# RelayModule_PWR.net
KiCad netlist of a schematic drawn in Altium Designer
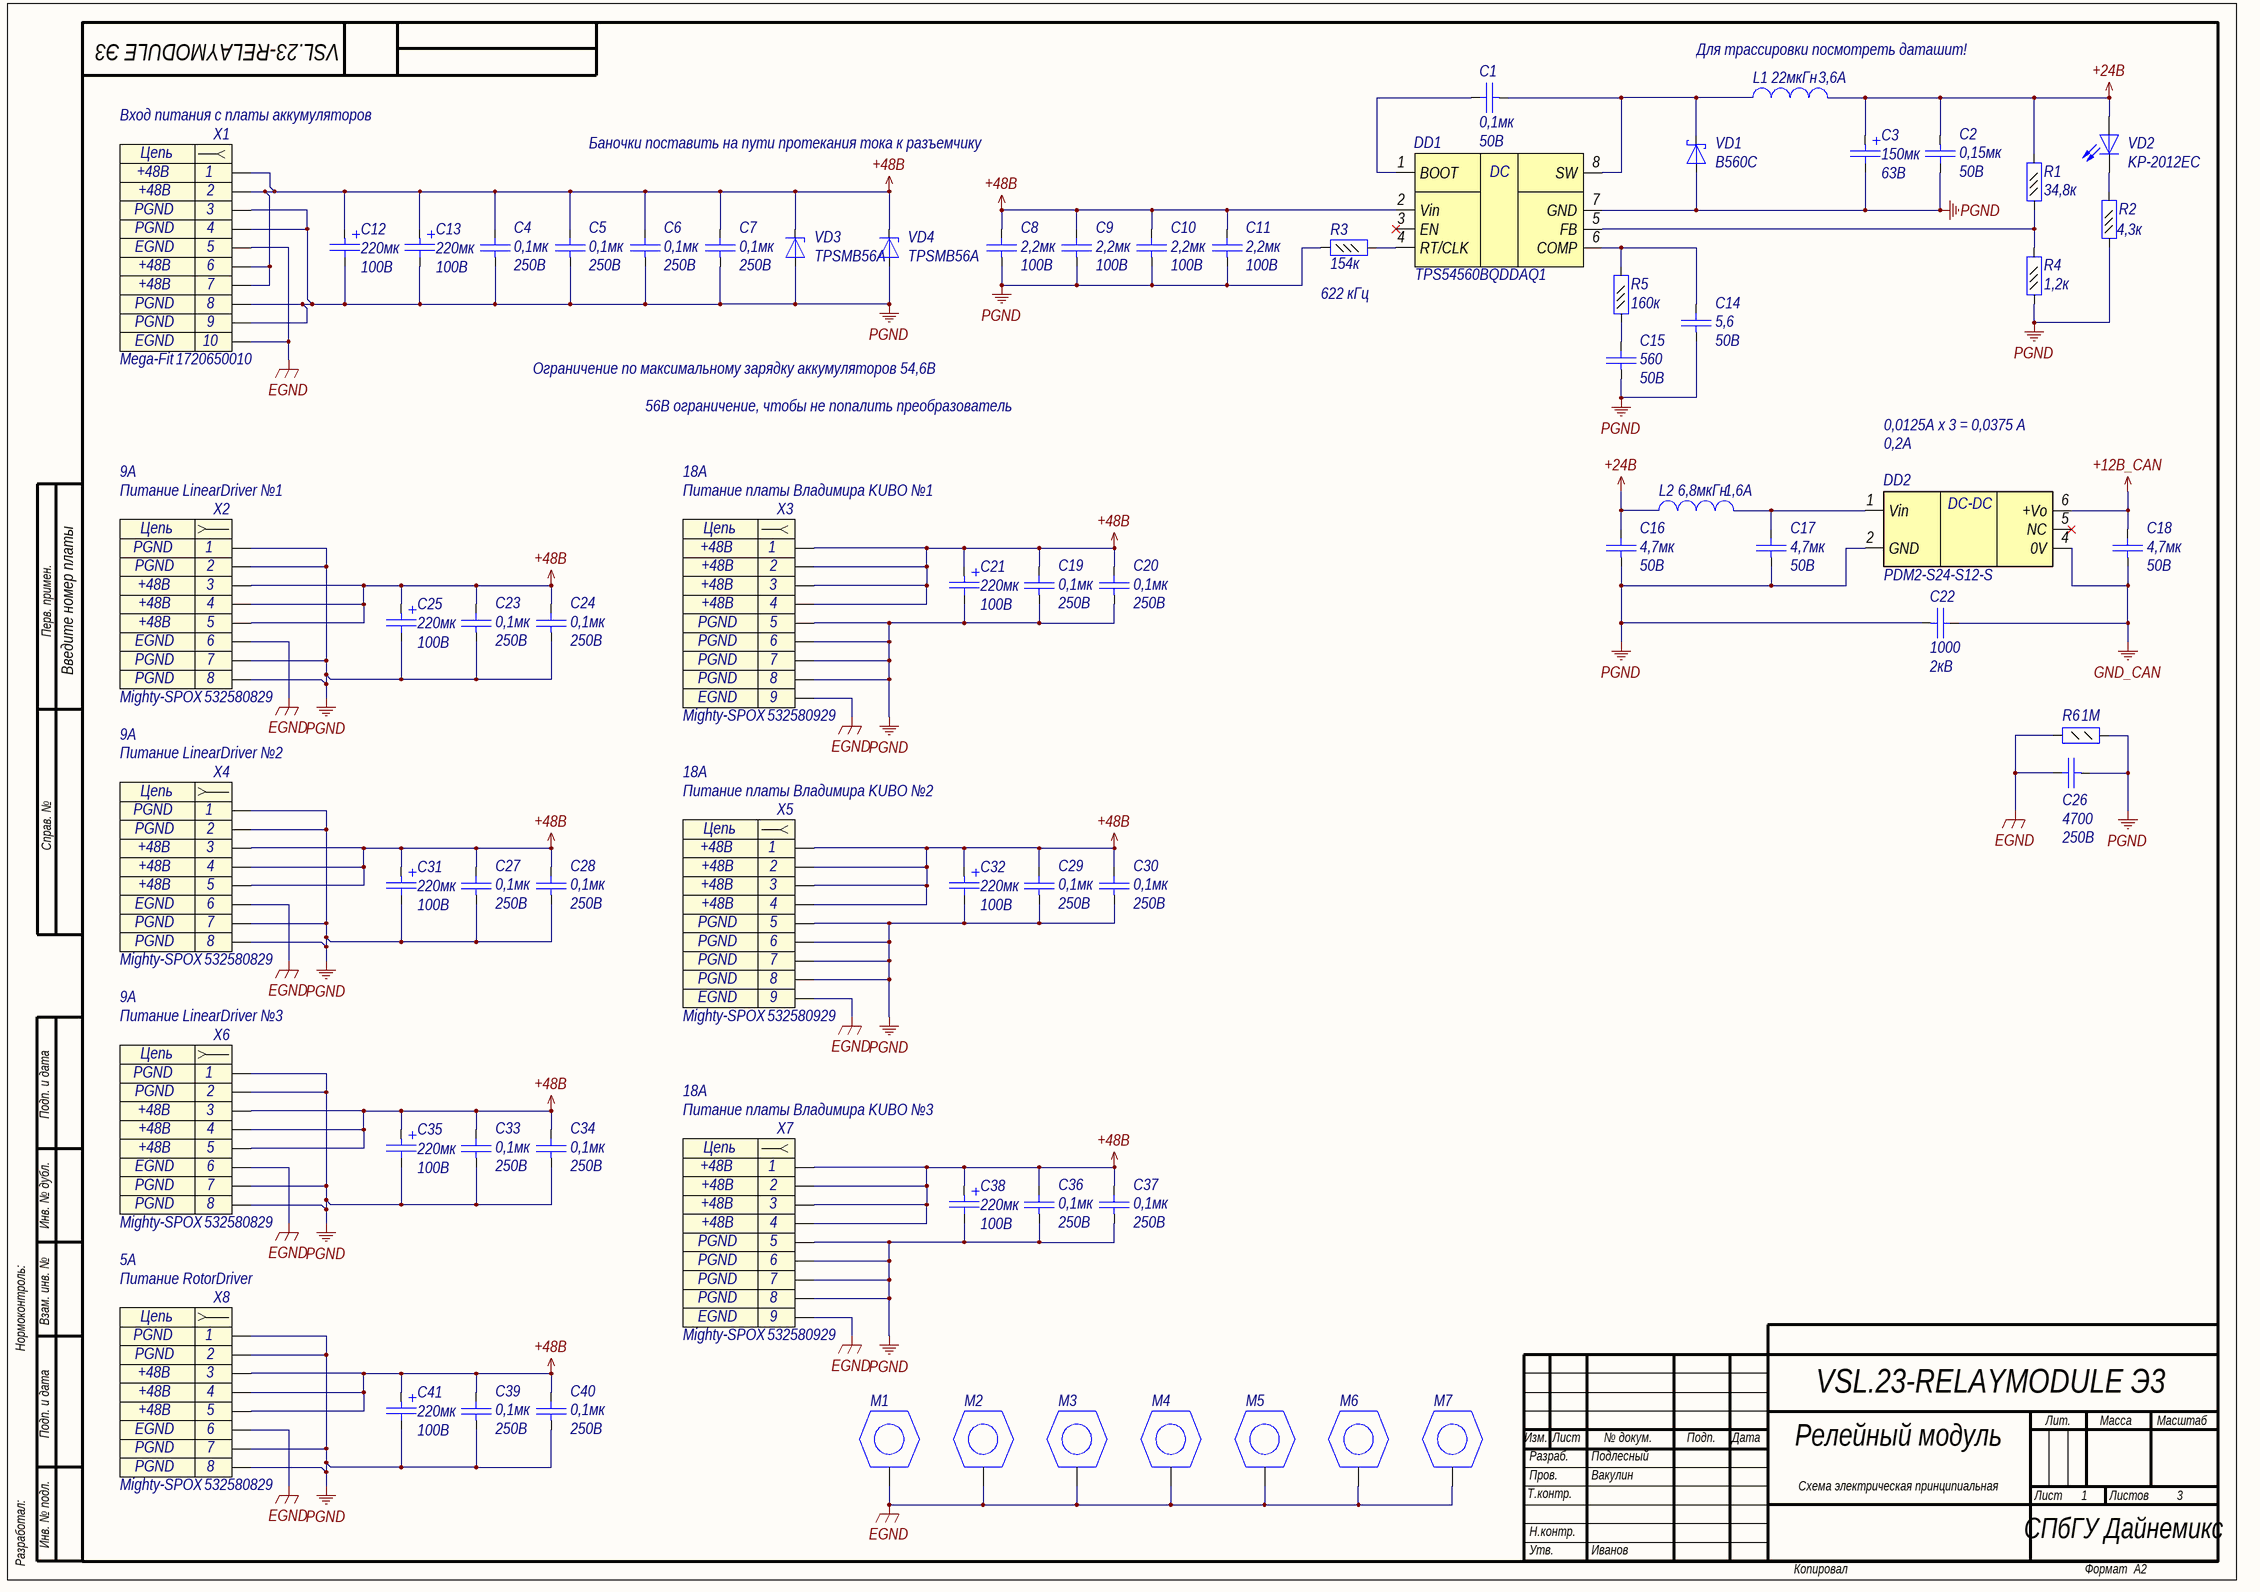
[diagram p0: RelayModule_PWR.SchDoc]

(export (version "E")
  (design (tool "Eeschema 10.0.6"))
  (components
    (comp (ref "C1")
      (value "0,1мк")
      (footprint "C0402")
      (description "Конденсатор")
      (fields (field (name "VOLTAGE") "50В") (field (name "PART NUMBER") "GRM155R71H104KE14D "))
      (libsource (lib "MOP44") (part "Capacitor"))
    )
    (comp (ref "C2")
      (value "0,15мк")
      (footprint "C1812")
      (description "Конденсатор")
      (fields (field (name "VOLTAGE") "50В") (field (name "PART NUMBER") "C4532C0G1H154J250KA "))
      (libsource (lib "MOP44") (part "Capacitor"))
    )
    (comp (ref "C3")
      (value "150мк")
      (footprint "Cap_SMD_radial_polar(10x16.5)")
      (description "Конденсатор полярный")
      (fields
        (field (name "VOLTAGE") "63B")
        (field (name "PART NUMBER") "EEH-ZS1J151P")
        (field (name "Comment") "Capacitor_pol")
      )
      (libsource (lib "MOP44") (part "Capacitor_pol"))
    )
    (comp (ref "C4")
      (value "0,1мк")
      (footprint "C1206")
      (description "Конденсатор")
      (fields
        (field (name "VOLTAGE") "250В")
        (field (name "PART NUMBER") "GRM31CR72E104K")
        (field (name "Comment") "Capacitor")
      )
      (libsource (lib "MOP44") (part "Capacitor"))
    )
    (comp (ref "C5")
      (value "0,1мк")
      (footprint "C1206")
      (description "Конденсатор")
      (fields
        (field (name "VOLTAGE") "250В")
        (field (name "PART NUMBER") "GRM31CR72E104K")
        (field (name "Comment") "Capacitor")
      )
      (libsource (lib "MOP44") (part "Capacitor"))
    )
    (comp (ref "C6")
      (value "0,1мк")
      (footprint "C1206")
      (description "Конденсатор")
      (fields
        (field (name "VOLTAGE") "250В")
        (field (name "PART NUMBER") "GRM31CR72E104K")
        (field (name "Comment") "Capacitor")
      )
      (libsource (lib "MOP44") (part "Capacitor"))
    )
    (comp (ref "C7")
      (value "0,1мк")
      (footprint "C1206")
      (description "Конденсатор")
      (fields
        (field (name "VOLTAGE") "250В")
        (field (name "PART NUMBER") "GRM31CR72E104K")
        (field (name "Comment") "Capacitor")
      )
      (libsource (lib "MOP44") (part "Capacitor"))
    )
    (comp (ref "C8")
      (value "2,2мк")
      (footprint "C1812")
      (description "Конденсатор")
      (fields (field (name "VOLTAGE") "100В") (field (name "PART NUMBER") "C4532X7R2A225M"))
      (libsource (lib "MOP44") (part "Capacitor"))
    )
    (comp (ref "C9")
      (value "2,2мк")
      (footprint "C1812")
      (description "Конденсатор")
      (fields (field (name "VOLTAGE") "100В") (field (name "PART NUMBER") "C4532X7R2A225M"))
      (libsource (lib "MOP44") (part "Capacitor"))
    )
    (comp (ref "C10")
      (value "2,2мк")
      (footprint "C1812")
      (description "Конденсатор")
      (fields (field (name "VOLTAGE") "100В") (field (name "PART NUMBER") "C4532X7R2A225M"))
      (libsource (lib "MOP44") (part "Capacitor"))
    )
    (comp (ref "C11")
      (value "2,2мк")
      (footprint "C1812")
      (description "Конденсатор")
      (fields (field (name "VOLTAGE") "100В") (field (name "PART NUMBER") "C4532X7R2A225M"))
      (libsource (lib "MOP44") (part "Capacitor"))
    )
    (comp (ref "C12")
      (value "220мк")
      (footprint "K50-35(12.5X25)_V")
      (description "Конденсатор полярный")
      (fields
        (field (name "VOLTAGE") "100B")
        (field (name "PART NUMBER") "B41851A9227M000")
        (field (name "Comment") "Capacitor_pol")
      )
      (libsource (lib "MOP44") (part "Capacitor_pol"))
    )
    (comp (ref "C13")
      (value "220мк")
      (footprint "K50-35(12.5X25)_V")
      (description "Конденсатор полярный")
      (fields
        (field (name "VOLTAGE") "100B")
        (field (name "PART NUMBER") "B41851A9227M000")
        (field (name "Comment") "Capacitor_pol")
      )
      (libsource (lib "MOP44") (part "Capacitor_pol"))
    )
    (comp (ref "C14")
      (value "5,6")
      (footprint "C0402")
      (description "Конденсатор")
      (fields (field (name "VOLTAGE") "50B") (field (name "PART NUMBER") "GRM1555C1H5R6C"))
      (libsource (lib "MOP44") (part "Capacitor"))
    )
    (comp (ref "C15")
      (value "560")
      (footprint "C0402")
      (description "Конденсатор")
      (fields (field (name "VOLTAGE") "50B") (field (name "PART NUMBER") "GRM1555C1H561J"))
      (libsource (lib "MOP44") (part "Capacitor"))
    )
    (comp (ref "C16")
      (value "4,7мк")
      (footprint "C1206")
      (description "Конденсатор")
      (fields (field (name "VOLTAGE") "50В") (field (name "PART NUMBER") "GRM31CR71H475KA12L"))
      (libsource (lib "MOP44") (part "Capacitor"))
    )
    (comp (ref "C17")
      (value "4,7мк")
      (footprint "C1206")
      (description "Конденсатор")
      (fields (field (name "VOLTAGE") "50В") (field (name "PART NUMBER") "GRM31CR71H475KA12L"))
      (libsource (lib "MOP44") (part "Capacitor"))
    )
    (comp (ref "C18")
      (value "4,7мк")
      (footprint "C1206")
      (description "Конденсатор")
      (fields (field (name "VOLTAGE") "50В") (field (name "PART NUMBER") "GRM31CR71H475KA12L"))
      (libsource (lib "MOP44") (part "Capacitor"))
    )
    (comp (ref "C19")
      (value "0,1мк")
      (footprint "C1206")
      (description "Конденсатор")
      (fields
        (field (name "VOLTAGE") "250В")
        (field (name "PART NUMBER") "GRM31CR72E104K")
        (field (name "Comment") "Capacitor")
      )
      (libsource (lib "MOP44") (part "Capacitor"))
    )
    (comp (ref "C20")
      (value "0,1мк")
      (footprint "C1206")
      (description "Конденсатор")
      (fields
        (field (name "VOLTAGE") "250В")
        (field (name "PART NUMBER") "GRM31CR72E104K")
        (field (name "Comment") "Capacitor")
      )
      (libsource (lib "MOP44") (part "Capacitor"))
    )
    (comp (ref "C21")
      (value "220мк")
      (footprint "K50-35(12.5X25)_V")
      (description "Конденсатор полярный")
      (fields
        (field (name "VOLTAGE") "100B")
        (field (name "PART NUMBER") "B41851A9227M000")
        (field (name "Comment") "Capacitor_pol")
      )
      (libsource (lib "MOP44") (part "Capacitor_pol"))
    )
    (comp (ref "C22")
      (value "1000")
      (footprint "C1808")
      (description "Конденсатор")
      (fields (field (name "VOLTAGE") "2кB") (field (name "PART NUMBER") "GR442QR73D102KW01L"))
      (libsource (lib "MOP44") (part "Capacitor"))
    )
    (comp (ref "C23")
      (value "0,1мк")
      (footprint "C1206")
      (description "Конденсатор")
      (fields
        (field (name "VOLTAGE") "250В")
        (field (name "PART NUMBER") "GRM31CR72E104K")
        (field (name "Comment") "Capacitor")
      )
      (libsource (lib "MOP44") (part "Capacitor"))
    )
    (comp (ref "C24")
      (value "0,1мк")
      (footprint "C1206")
      (description "Конденсатор")
      (fields
        (field (name "VOLTAGE") "250В")
        (field (name "PART NUMBER") "GRM31CR72E104K")
        (field (name "Comment") "Capacitor")
      )
      (libsource (lib "MOP44") (part "Capacitor"))
    )
    (comp (ref "C25")
      (value "220мк")
      (footprint "K50-35(12.5X25)_V")
      (description "Конденсатор полярный")
      (fields
        (field (name "VOLTAGE") "100B")
        (field (name "PART NUMBER") "B41851A9227M000")
        (field (name "Comment") "Capacitor_pol")
      )
      (libsource (lib "MOP44") (part "Capacitor_pol"))
    )
    (comp (ref "C26")
      (value "4700")
      (footprint "C0805")
      (description "Конденсатор")
      (fields
        (field (name "VOLTAGE") "250В")
        (field (name "PART NUMBER") "GRM21AR72E472KW")
        (field (name "Comment") "Capacitor")
      )
      (libsource (lib "MOP44") (part "Capacitor"))
    )
    (comp (ref "C27")
      (value "0,1мк")
      (footprint "C1206")
      (description "Конденсатор")
      (fields
        (field (name "VOLTAGE") "250В")
        (field (name "PART NUMBER") "GRM31CR72E104K")
        (field (name "Comment") "Capacitor")
      )
      (libsource (lib "MOP44") (part "Capacitor"))
    )
    (comp (ref "C28")
      (value "0,1мк")
      (footprint "C1206")
      (description "Конденсатор")
      (fields
        (field (name "VOLTAGE") "250В")
        (field (name "PART NUMBER") "GRM31CR72E104K")
        (field (name "Comment") "Capacitor")
      )
      (libsource (lib "MOP44") (part "Capacitor"))
    )
    (comp (ref "C29")
      (value "0,1мк")
      (footprint "C1206")
      (description "Конденсатор")
      (fields
        (field (name "VOLTAGE") "250В")
        (field (name "PART NUMBER") "GRM31CR72E104K")
        (field (name "Comment") "Capacitor")
      )
      (libsource (lib "MOP44") (part "Capacitor"))
    )
    (comp (ref "C30")
      (value "0,1мк")
      (footprint "C1206")
      (description "Конденсатор")
      (fields
        (field (name "VOLTAGE") "250В")
        (field (name "PART NUMBER") "GRM31CR72E104K")
        (field (name "Comment") "Capacitor")
      )
      (libsource (lib "MOP44") (part "Capacitor"))
    )
    (comp (ref "C31")
      (value "220мк")
      (footprint "K50-35(12.5X25)_V")
      (description "Конденсатор полярный")
      (fields
        (field (name "VOLTAGE") "100B")
        (field (name "PART NUMBER") "B41851A9227M000")
        (field (name "Comment") "Capacitor_pol")
      )
      (libsource (lib "MOP44") (part "Capacitor_pol"))
    )
    (comp (ref "C32")
      (value "220мк")
      (footprint "K50-35(12.5X25)_V")
      (description "Конденсатор полярный")
      (fields
        (field (name "VOLTAGE") "100B")
        (field (name "PART NUMBER") "B41851A9227M000")
        (field (name "Comment") "Capacitor_pol")
      )
      (libsource (lib "MOP44") (part "Capacitor_pol"))
    )
    (comp (ref "C33")
      (value "0,1мк")
      (footprint "C1206")
      (description "Конденсатор")
      (fields
        (field (name "VOLTAGE") "250В")
        (field (name "PART NUMBER") "GRM31CR72E104K")
        (field (name "Comment") "Capacitor")
      )
      (libsource (lib "MOP44") (part "Capacitor"))
    )
    (comp (ref "C34")
      (value "0,1мк")
      (footprint "C1206")
      (description "Конденсатор")
      (fields
        (field (name "VOLTAGE") "250В")
        (field (name "PART NUMBER") "GRM31CR72E104K")
        (field (name "Comment") "Capacitor")
      )
      (libsource (lib "MOP44") (part "Capacitor"))
    )
    (comp (ref "C35")
      (value "220мк")
      (footprint "K50-35(12.5X25)_V")
      (description "Конденсатор полярный")
      (fields
        (field (name "VOLTAGE") "100B")
        (field (name "PART NUMBER") "B41851A9227M000")
        (field (name "Comment") "Capacitor_pol")
      )
      (libsource (lib "MOP44") (part "Capacitor_pol"))
    )
    (comp (ref "C36")
      (value "0,1мк")
      (footprint "C1206")
      (description "Конденсатор")
      (fields
        (field (name "VOLTAGE") "250В")
        (field (name "PART NUMBER") "GRM31CR72E104K")
        (field (name "Comment") "Capacitor")
      )
      (libsource (lib "MOP44") (part "Capacitor"))
    )
    (comp (ref "C37")
      (value "0,1мк")
      (footprint "C1206")
      (description "Конденсатор")
      (fields
        (field (name "VOLTAGE") "250В")
        (field (name "PART NUMBER") "GRM31CR72E104K")
        (field (name "Comment") "Capacitor")
      )
      (libsource (lib "MOP44") (part "Capacitor"))
    )
    (comp (ref "C38")
      (value "220мк")
      (footprint "K50-35(12.5X25)_V")
      (description "Конденсатор полярный")
      (fields
        (field (name "VOLTAGE") "100B")
        (field (name "PART NUMBER") "B41851A9227M000")
        (field (name "Comment") "Capacitor_pol")
      )
      (libsource (lib "MOP44") (part "Capacitor_pol"))
    )
    (comp (ref "C39")
      (value "0,1мк")
      (footprint "C1206")
      (description "Конденсатор")
      (fields
        (field (name "VOLTAGE") "250В")
        (field (name "PART NUMBER") "GRM31CR72E104K")
        (field (name "Comment") "Capacitor")
      )
      (libsource (lib "MOP44") (part "Capacitor"))
    )
    (comp (ref "C40")
      (value "0,1мк")
      (footprint "C1206")
      (description "Конденсатор")
      (fields
        (field (name "VOLTAGE") "250В")
        (field (name "PART NUMBER") "GRM31CR72E104K")
        (field (name "Comment") "Capacitor")
      )
      (libsource (lib "MOP44") (part "Capacitor"))
    )
    (comp (ref "C41")
      (value "220мк")
      (footprint "K50-35(12.5X25)_V")
      (description "Конденсатор полярный")
      (fields
        (field (name "VOLTAGE") "100B")
        (field (name "PART NUMBER") "B41851A9227M000")
        (field (name "Comment") "Capacitor_pol")
      )
      (libsource (lib "MOP44") (part "Capacitor_pol"))
    )
    (comp (ref "DD1")
      (value "TPS54560")
      (footprint "SO Powerpad8")
      (description "5-A, Wide Input Range, Step-Down Converter")
      (fields
        (field (name "PART NUMBER") "TPS54560BQDDAQ1")
        (field (name "MANUFACTURER") "Texas Instruments")
      )
      (libsource (lib "MOP44") (part "TPS54560"))
    )
    (comp (ref "DD2")
      (value "PDM2-Sxx-Sxx-S")
      (footprint "SIP6")
      (description "DC/DC преобразователь изолированный")
      (fields (field (name "PART NUMBER") "PDM2-S24-S12-S") (field (name "MANUFACTURER") "CUI INC"))
      (libsource (lib "MOP44") (part "PDM2-Sxx-Sxx-S"))
    )
    (comp (ref "L1")
      (value "22мкГн")
      (footprint "IND_12.5x12.5")
      (description "EMI Suppression Filter")
      (fields
        (field (name "RATED CURRENT") "3,6A")
        (field (name "PART NUMBER") "B82477G4223M000")
        (field (name "Comment") "Inductor")
      )
      (libsource (lib "MOP44") (part "Inductor"))
    )
    (comp (ref "L2")
      (value "6,8мкГн")
      (footprint "SDR0604")
      (description "EMI Suppression Filter")
      (fields
        (field (name "RATED CURRENT") "1,6A")
        (field (name "PART NUMBER") "SDR0604-6R8ML")
        (field (name "Comment") "Inductor")
      )
      (libsource (lib "MOP44") (part "Inductor"))
    )
    (comp (ref "M1") (value "SCREW") (footprint "SCREW3") (libsource (lib "MOP44") (part "SCREW")))
    (comp (ref "M2") (value "SCREW") (footprint "SCREW3") (libsource (lib "MOP44") (part "SCREW")))
    (comp (ref "M3") (value "SCREW") (footprint "SCREW3") (libsource (lib "MOP44") (part "SCREW")))
    (comp (ref "M4") (value "SCREW") (footprint "SCREW3") (libsource (lib "MOP44") (part "SCREW")))
    (comp (ref "M5") (value "SCREW") (footprint "SCREW3") (libsource (lib "MOP44") (part "SCREW")))
    (comp (ref "M6") (value "SCREW") (footprint "SCREW3") (libsource (lib "MOP44") (part "SCREW")))
    (comp (ref "M7") (value "SCREW") (footprint "SCREW3") (libsource (lib "MOP44") (part "SCREW")))
    (comp (ref "R1")
      (value "34,8к")
      (footprint "R0402")
      (description "Резистор")
      (fields (field (name "PART NUMBER") "RC0402FR-0734K8L") (field (name "POWER") "0,062Вт"))
      (libsource (lib "MOP44") (part "Resistor_0,062Вт"))
    )
    (comp (ref "R2")
      (value "4,3к")
      (footprint "R0402")
      (description "Резистор")
      (fields (field (name "PART NUMBER") "RC0402FR-074K3") (field (name "POWER") "0,062Вт"))
      (libsource (lib "MOP44") (part "Resistor_0,062Вт"))
    )
    (comp (ref "R3")
      (value "154к")
      (footprint "R0402")
      (description "Резистор")
      (fields (field (name "PART NUMBER") "RC0402FR-07154KL") (field (name "POWER") "0,062Вт"))
      (libsource (lib "") (part "Resistor_0,062Вт_1"))
    )
    (comp (ref "R4")
      (value "1,2к")
      (footprint "R0402")
      (description "Резистор")
      (fields (field (name "PART NUMBER") "RC0402FR-071K2") (field (name "POWER") "0,062Вт"))
      (libsource (lib "MOP44") (part "Resistor_0,062Вт"))
    )
    (comp (ref "R5")
      (value "160к")
      (footprint "R0402")
      (description "Резистор")
      (fields (field (name "PART NUMBER") "RC0402FR-07160KL") (field (name "POWER") "0,062Вт"))
      (libsource (lib "MOP44") (part "Resistor_0,062Вт"))
    )
    (comp (ref "R6")
      (value "1М")
      (footprint "R0805")
      (description "Резистор")
      (fields (field (name "PART NUMBER") "RC0805FR-071ML") (field (name "POWER") "0,125Вт"))
      (libsource (lib "MOP44") (part "Resistor_0,125Вт"))
    )
    (comp (ref "VD1")
      (value "DiodeSchottky")
      (footprint "SMC")
      (description "Диод Шоттки")
      (fields (field (name "PART NUMBER") "B560C"))
      (libsource (lib "MOP44") (part "DiodeSchottky"))
    )
    (comp (ref "VD2")
      (value "LED")
      (footprint "L_0805")
      (description "Светодиод")
      (fields (field (name "PART NUMBER") "KP-2012EC"))
      (libsource (lib "MOP44") (part "LED"))
    )
    (comp (ref "VD3")
      (value "DiodeZener")
      (footprint "SMB")
      (description "Cтабилитрон (лавинный выпрямительный диод) односторонний")
      (fields (field (name "PART NUMBER") "TPSMB56A"))
      (libsource (lib "MOP44") (part "DiodeZener"))
    )
    (comp (ref "VD4")
      (value "DiodeZener")
      (footprint "SMB")
      (description "Cтабилитрон (лавинный выпрямительный диод) односторонний")
      (fields (field (name "PART NUMBER") "TPSMB56A"))
      (libsource (lib "MOP44") (part "DiodeZener"))
    )
    (comp (ref "X1")
      (value "Вход питания с платы аккумуляторов")
      (footprint "MOLEX_1720650010")
      (description "Разъем - 10 конт. розетка")
      (fields (field (name "PART NAME") "Mega-Fit") (field (name "PART NUMBER") "1720650010"))
      (libsource (lib "MOP44") (part "Header_10_sct"))
    )
    (comp (ref "X2")
      (value "Питание LinearDriver №1")
      (footprint "MOLEX_532580829")
      (description "Разъем - 8 конт. розетка")
      (fields (field (name "PART NAME") "Mighty-SPOX") (field (name "PART NUMBER") "532580829"))
      (libsource (lib "MOP44") (part "Header_8_sct"))
    )
    (comp (ref "X3")
      (value "Питание платы Владимира KUBO №1")
      (footprint "MOLEX_532580929")
      (description "Разъем - 9 конт. розетка")
      (fields (field (name "PART NAME") "Mighty-SPOX") (field (name "PART NUMBER") "532580929"))
      (libsource (lib "MOP44") (part "Header_9_sct"))
    )
    (comp (ref "X4")
      (value "Питание LinearDriver №2")
      (footprint "MOLEX_532580829")
      (description "Разъем - 8 конт. розетка")
      (fields (field (name "PART NAME") "Mighty-SPOX") (field (name "PART NUMBER") "532580829"))
      (libsource (lib "MOP44") (part "Header_8_sct"))
    )
    (comp (ref "X5")
      (value "Питание платы Владимира KUBO №2")
      (footprint "MOLEX_532580929")
      (description "Разъем - 9 конт. розетка")
      (fields (field (name "PART NAME") "Mighty-SPOX") (field (name "PART NUMBER") "532580929"))
      (libsource (lib "MOP44") (part "Header_9_sct"))
    )
    (comp (ref "X6")
      (value "Питание LinearDriver №3")
      (footprint "MOLEX_532580829")
      (description "Разъем - 8 конт. розетка")
      (fields (field (name "PART NAME") "Mighty-SPOX") (field (name "PART NUMBER") "532580829"))
      (libsource (lib "MOP44") (part "Header_8_sct"))
    )
    (comp (ref "X7")
      (value "Питание платы Владимира KUBO №3")
      (footprint "MOLEX_532580929")
      (description "Разъем - 9 конт. розетка")
      (fields (field (name "PART NAME") "Mighty-SPOX") (field (name "PART NUMBER") "532580929"))
      (libsource (lib "MOP44") (part "Header_9_sct"))
    )
    (comp (ref "X8")
      (value "Питание RotorDriver")
      (footprint "MOLEX_532580829")
      (description "Разъем - 8 конт. розетка")
      (fields (field (name "PART NAME") "Mighty-SPOX") (field (name "PART NUMBER") "532580829"))
      (libsource (lib "MOP44") (part "Header_8_sct"))
    )
  )
  (nets
    (net (code "1") (name "+12B_CAN") (class "Default")
      (node (ref "C18") (pin "2") (pinfunction "2_2") (pintype "passive"))
      (node (ref "DD2") (pin "6") (pinfunction "+Vo_6") (pintype "passive"))
    )
    (net (code "2") (name "+24B") (class "Default")
      (node (ref "C16") (pin "2") (pinfunction "2_2") (pintype "passive"))
      (node (ref "C2") (pin "1") (pinfunction "1_1") (pintype "passive"))
      (node (ref "C3") (pin "1") (pinfunction "1_1") (pintype "passive"))
      (node (ref "L1") (pin "2") (pinfunction "2_2") (pintype "passive"))
      (node (ref "L2") (pin "1") (pinfunction "1_1") (pintype "passive"))
      (node (ref "R1") (pin "2") (pinfunction "2_2") (pintype "passive"))
      (node (ref "VD2") (pin "2") (pinfunction "A_2") (pintype "passive"))
    )
    (net (code "3") (name "+48B") (class "Default")
      (node (ref "C10") (pin "2") (pinfunction "2_2") (pintype "passive"))
      (node (ref "C11") (pin "2") (pinfunction "2_2") (pintype "passive"))
      (node (ref "C12") (pin "1") (pinfunction "1_1") (pintype "passive"))
      (node (ref "C13") (pin "1") (pinfunction "1_1") (pintype "passive"))
      (node (ref "C19") (pin "2") (pinfunction "2_2") (pintype "passive"))
      (node (ref "C20") (pin "2") (pinfunction "2_2") (pintype "passive"))
      (node (ref "C21") (pin "1") (pinfunction "1_1") (pintype "passive"))
      (node (ref "C23") (pin "2") (pinfunction "2_2") (pintype "passive"))
      (node (ref "C24") (pin "2") (pinfunction "2_2") (pintype "passive"))
      (node (ref "C25") (pin "1") (pinfunction "1_1") (pintype "passive"))
      (node (ref "C27") (pin "2") (pinfunction "2_2") (pintype "passive"))
      (node (ref "C28") (pin "2") (pinfunction "2_2") (pintype "passive"))
      (node (ref "C29") (pin "2") (pinfunction "2_2") (pintype "passive"))
      (node (ref "C30") (pin "2") (pinfunction "2_2") (pintype "passive"))
      (node (ref "C31") (pin "1") (pinfunction "1_1") (pintype "passive"))
      (node (ref "C32") (pin "1") (pinfunction "1_1") (pintype "passive"))
      (node (ref "C33") (pin "2") (pinfunction "2_2") (pintype "passive"))
      (node (ref "C34") (pin "2") (pinfunction "2_2") (pintype "passive"))
      (node (ref "C35") (pin "1") (pinfunction "1_1") (pintype "passive"))
      (node (ref "C36") (pin "2") (pinfunction "2_2") (pintype "passive"))
      (node (ref "C37") (pin "2") (pinfunction "2_2") (pintype "passive"))
      (node (ref "C38") (pin "1") (pinfunction "1_1") (pintype "passive"))
      (node (ref "C39") (pin "2") (pinfunction "2_2") (pintype "passive"))
      (node (ref "C4") (pin "2") (pinfunction "2_2") (pintype "passive"))
      (node (ref "C40") (pin "2") (pinfunction "2_2") (pintype "passive"))
      (node (ref "C41") (pin "1") (pinfunction "1_1") (pintype "passive"))
      (node (ref "C5") (pin "2") (pinfunction "2_2") (pintype "passive"))
      (node (ref "C6") (pin "2") (pinfunction "2_2") (pintype "passive"))
      (node (ref "C7") (pin "2") (pinfunction "2_2") (pintype "passive"))
      (node (ref "C8") (pin "2") (pinfunction "2_2") (pintype "passive"))
      (node (ref "C9") (pin "2") (pinfunction "2_2") (pintype "passive"))
      (node (ref "DD1") (pin "2") (pinfunction "Vin_2") (pintype "passive"))
      (node (ref "VD3") (pin "1") (pinfunction "K_1") (pintype "passive"))
      (node (ref "VD4") (pin "1") (pinfunction "K_1") (pintype "passive"))
      (node (ref "X1") (pin "1") (pinfunction "1_1") (pintype "passive"))
      (node (ref "X1") (pin "2") (pinfunction "2_2") (pintype "passive"))
      (node (ref "X1") (pin "6") (pinfunction "6_6") (pintype "passive"))
      (node (ref "X1") (pin "7") (pinfunction "7_7") (pintype "passive"))
      (node (ref "X2") (pin "3") (pinfunction "3_3") (pintype "passive"))
      (node (ref "X2") (pin "4") (pinfunction "4_4") (pintype "passive"))
      (node (ref "X2") (pin "5") (pinfunction "5_5") (pintype "passive"))
      (node (ref "X3") (pin "1") (pinfunction "1_1") (pintype "passive"))
      (node (ref "X3") (pin "2") (pinfunction "2_2") (pintype "passive"))
      (node (ref "X3") (pin "3") (pinfunction "3_3") (pintype "passive"))
      (node (ref "X3") (pin "4") (pinfunction "4_4") (pintype "passive"))
      (node (ref "X4") (pin "3") (pinfunction "3_3") (pintype "passive"))
      (node (ref "X4") (pin "4") (pinfunction "4_4") (pintype "passive"))
      (node (ref "X4") (pin "5") (pinfunction "5_5") (pintype "passive"))
      (node (ref "X5") (pin "1") (pinfunction "1_1") (pintype "passive"))
      (node (ref "X5") (pin "2") (pinfunction "2_2") (pintype "passive"))
      (node (ref "X5") (pin "3") (pinfunction "3_3") (pintype "passive"))
      (node (ref "X5") (pin "4") (pinfunction "4_4") (pintype "passive"))
      (node (ref "X6") (pin "3") (pinfunction "3_3") (pintype "passive"))
      (node (ref "X6") (pin "4") (pinfunction "4_4") (pintype "passive"))
      (node (ref "X6") (pin "5") (pinfunction "5_5") (pintype "passive"))
      (node (ref "X7") (pin "1") (pinfunction "1_1") (pintype "passive"))
      (node (ref "X7") (pin "2") (pinfunction "2_2") (pintype "passive"))
      (node (ref "X7") (pin "3") (pinfunction "3_3") (pintype "passive"))
      (node (ref "X7") (pin "4") (pinfunction "4_4") (pintype "passive"))
      (node (ref "X8") (pin "3") (pinfunction "3_3") (pintype "passive"))
      (node (ref "X8") (pin "4") (pinfunction "4_4") (pintype "passive"))
      (node (ref "X8") (pin "5") (pinfunction "5_5") (pintype "passive"))
    )
    (net (code "4") (name "EGND") (class "Default")
      (node (ref "C26") (pin "2") (pinfunction "2_2") (pintype "passive"))
      (node (ref "M1") (pin "1") (pinfunction "1_1") (pintype "passive"))
      (node (ref "M2") (pin "1") (pinfunction "1_1") (pintype "passive"))
      (node (ref "M3") (pin "1") (pinfunction "1_1") (pintype "passive"))
      (node (ref "M4") (pin "1") (pinfunction "1_1") (pintype "passive"))
      (node (ref "M5") (pin "1") (pinfunction "1_1") (pintype "passive"))
      (node (ref "M6") (pin "1") (pinfunction "1_1") (pintype "passive"))
      (node (ref "M7") (pin "1") (pinfunction "1_1") (pintype "passive"))
      (node (ref "R6") (pin "2") (pinfunction "2_2") (pintype "passive"))
      (node (ref "X1") (pin "10") (pinfunction "10_10") (pintype "passive"))
      (node (ref "X1") (pin "5") (pinfunction "5_5") (pintype "passive"))
      (node (ref "X2") (pin "6") (pinfunction "6_6") (pintype "passive"))
      (node (ref "X3") (pin "9") (pinfunction "9_9") (pintype "passive"))
      (node (ref "X4") (pin "6") (pinfunction "6_6") (pintype "passive"))
      (node (ref "X5") (pin "9") (pinfunction "9_9") (pintype "passive"))
      (node (ref "X6") (pin "6") (pinfunction "6_6") (pintype "passive"))
      (node (ref "X7") (pin "9") (pinfunction "9_9") (pintype "passive"))
      (node (ref "X8") (pin "6") (pinfunction "6_6") (pintype "passive"))
    )
    (net (code "5") (name "GND_CAN") (class "Default")
      (node (ref "C18") (pin "1") (pinfunction "1_1") (pintype "passive"))
      (node (ref "C22") (pin "2") (pinfunction "2_2") (pintype "passive"))
      (node (ref "DD2") (pin "4") (pinfunction "0V_4") (pintype "passive"))
    )
    (net (code "6") (name "Net-(C15-Pad2)") (class "Default")
      (node (ref "C15") (pin "2") (pinfunction "2_2") (pintype "passive"))
      (node (ref "R5") (pin "1") (pinfunction "1_1") (pintype "passive"))
    )
    (net (code "7") (name "Net-(DD1-BOOT)") (class "Default")
      (node (ref "C1") (pin "2") (pinfunction "2_2") (pintype "passive"))
      (node (ref "DD1") (pin "1") (pinfunction "BOOT_1") (pintype "passive"))
    )
    (net (code "8") (name "Net-(DD1-COMP)") (class "Default")
      (node (ref "C14") (pin "2") (pinfunction "2_2") (pintype "passive"))
      (node (ref "DD1") (pin "6") (pinfunction "COMP_6") (pintype "passive"))
      (node (ref "R5") (pin "2") (pinfunction "2_2") (pintype "passive"))
    )
    (net (code "9") (name "Net-(DD1-FB)") (class "Default")
      (node (ref "DD1") (pin "5") (pinfunction "FB_5") (pintype "passive"))
      (node (ref "R1") (pin "1") (pinfunction "1_1") (pintype "passive"))
      (node (ref "R4") (pin "2") (pinfunction "2_2") (pintype "passive"))
    )
    (net (code "10") (name "Net-(DD1-RT{slash}CLK)") (class "Default")
      (node (ref "DD1") (pin "4") (pinfunction "RT/CLK_4") (pintype "passive"))
      (node (ref "R3") (pin "2") (pinfunction "2_2") (pintype "passive"))
    )
    (net (code "11") (name "Net-(DD1-SW)") (class "Default")
      (node (ref "C1") (pin "1") (pinfunction "1_1") (pintype "passive"))
      (node (ref "DD1") (pin "8") (pinfunction "SW_8") (pintype "passive"))
      (node (ref "L1") (pin "1") (pinfunction "1_1") (pintype "passive"))
      (node (ref "VD1") (pin "1") (pinfunction "K_1") (pintype "passive"))
    )
    (net (code "12") (name "Net-(DD2-Vin)") (class "Default")
      (node (ref "C17") (pin "2") (pinfunction "2_2") (pintype "passive"))
      (node (ref "DD2") (pin "1") (pinfunction "Vin_1") (pintype "passive"))
      (node (ref "L2") (pin "2") (pinfunction "2_2") (pintype "passive"))
    )
    (net (code "13") (name "Net-(VD2-K)") (class "Default")
      (node (ref "R2") (pin "2") (pinfunction "2_2") (pintype "passive"))
      (node (ref "VD2") (pin "1") (pinfunction "K_1") (pintype "passive"))
    )
    (net (code "14") (name "PGND") (class "Default")
      (node (ref "C10") (pin "1") (pinfunction "1_1") (pintype "passive"))
      (node (ref "C11") (pin "1") (pinfunction "1_1") (pintype "passive"))
      (node (ref "C12") (pin "2") (pinfunction "2_2") (pintype "passive"))
      (node (ref "C13") (pin "2") (pinfunction "2_2") (pintype "passive"))
      (node (ref "C14") (pin "1") (pinfunction "1_1") (pintype "passive"))
      (node (ref "C15") (pin "1") (pinfunction "1_1") (pintype "passive"))
      (node (ref "C16") (pin "1") (pinfunction "1_1") (pintype "passive"))
      (node (ref "C17") (pin "1") (pinfunction "1_1") (pintype "passive"))
      (node (ref "C19") (pin "1") (pinfunction "1_1") (pintype "passive"))
      (node (ref "C2") (pin "2") (pinfunction "2_2") (pintype "passive"))
      (node (ref "C20") (pin "1") (pinfunction "1_1") (pintype "passive"))
      (node (ref "C21") (pin "2") (pinfunction "2_2") (pintype "passive"))
      (node (ref "C22") (pin "1") (pinfunction "1_1") (pintype "passive"))
      (node (ref "C23") (pin "1") (pinfunction "1_1") (pintype "passive"))
      (node (ref "C24") (pin "1") (pinfunction "1_1") (pintype "passive"))
      (node (ref "C25") (pin "2") (pinfunction "2_2") (pintype "passive"))
      (node (ref "C26") (pin "1") (pinfunction "1_1") (pintype "passive"))
      (node (ref "C27") (pin "1") (pinfunction "1_1") (pintype "passive"))
      (node (ref "C28") (pin "1") (pinfunction "1_1") (pintype "passive"))
      (node (ref "C29") (pin "1") (pinfunction "1_1") (pintype "passive"))
      (node (ref "C3") (pin "2") (pinfunction "2_2") (pintype "passive"))
      (node (ref "C30") (pin "1") (pinfunction "1_1") (pintype "passive"))
      (node (ref "C31") (pin "2") (pinfunction "2_2") (pintype "passive"))
      (node (ref "C32") (pin "2") (pinfunction "2_2") (pintype "passive"))
      (node (ref "C33") (pin "1") (pinfunction "1_1") (pintype "passive"))
      (node (ref "C34") (pin "1") (pinfunction "1_1") (pintype "passive"))
      (node (ref "C35") (pin "2") (pinfunction "2_2") (pintype "passive"))
      (node (ref "C36") (pin "1") (pinfunction "1_1") (pintype "passive"))
      (node (ref "C37") (pin "1") (pinfunction "1_1") (pintype "passive"))
      (node (ref "C38") (pin "2") (pinfunction "2_2") (pintype "passive"))
      (node (ref "C39") (pin "1") (pinfunction "1_1") (pintype "passive"))
      (node (ref "C4") (pin "1") (pinfunction "1_1") (pintype "passive"))
      (node (ref "C40") (pin "1") (pinfunction "1_1") (pintype "passive"))
      (node (ref "C41") (pin "2") (pinfunction "2_2") (pintype "passive"))
      (node (ref "C5") (pin "1") (pinfunction "1_1") (pintype "passive"))
      (node (ref "C6") (pin "1") (pinfunction "1_1") (pintype "passive"))
      (node (ref "C7") (pin "1") (pinfunction "1_1") (pintype "passive"))
      (node (ref "C8") (pin "1") (pinfunction "1_1") (pintype "passive"))
      (node (ref "C9") (pin "1") (pinfunction "1_1") (pintype "passive"))
      (node (ref "DD1") (pin "7") (pinfunction "GND_7") (pintype "passive"))
      (node (ref "DD2") (pin "2") (pinfunction "GND_2") (pintype "passive"))
      (node (ref "R2") (pin "1") (pinfunction "1_1") (pintype "passive"))
      (node (ref "R3") (pin "1") (pinfunction "1_1") (pintype "passive"))
      (node (ref "R4") (pin "1") (pinfunction "1_1") (pintype "passive"))
      (node (ref "R6") (pin "1") (pinfunction "1_1") (pintype "passive"))
      (node (ref "VD1") (pin "2") (pinfunction "A_2") (pintype "passive"))
      (node (ref "VD3") (pin "2") (pinfunction "A_2") (pintype "passive"))
      (node (ref "VD4") (pin "2") (pinfunction "A_2") (pintype "passive"))
      (node (ref "X1") (pin "3") (pinfunction "3_3") (pintype "passive"))
      (node (ref "X1") (pin "4") (pinfunction "4_4") (pintype "passive"))
      (node (ref "X1") (pin "8") (pinfunction "8_8") (pintype "passive"))
      (node (ref "X1") (pin "9") (pinfunction "9_9") (pintype "passive"))
      (node (ref "X2") (pin "1") (pinfunction "1_1") (pintype "passive"))
      (node (ref "X2") (pin "2") (pinfunction "2_2") (pintype "passive"))
      (node (ref "X2") (pin "7") (pinfunction "7_7") (pintype "passive"))
      (node (ref "X2") (pin "8") (pinfunction "8_8") (pintype "passive"))
      (node (ref "X3") (pin "5") (pinfunction "5_5") (pintype "passive"))
      (node (ref "X3") (pin "6") (pinfunction "6_6") (pintype "passive"))
      (node (ref "X3") (pin "7") (pinfunction "7_7") (pintype "passive"))
      (node (ref "X3") (pin "8") (pinfunction "8_8") (pintype "passive"))
      (node (ref "X4") (pin "1") (pinfunction "1_1") (pintype "passive"))
      (node (ref "X4") (pin "2") (pinfunction "2_2") (pintype "passive"))
      (node (ref "X4") (pin "7") (pinfunction "7_7") (pintype "passive"))
      (node (ref "X4") (pin "8") (pinfunction "8_8") (pintype "passive"))
      (node (ref "X5") (pin "5") (pinfunction "5_5") (pintype "passive"))
      (node (ref "X5") (pin "6") (pinfunction "6_6") (pintype "passive"))
      (node (ref "X5") (pin "7") (pinfunction "7_7") (pintype "passive"))
      (node (ref "X5") (pin "8") (pinfunction "8_8") (pintype "passive"))
      (node (ref "X6") (pin "1") (pinfunction "1_1") (pintype "passive"))
      (node (ref "X6") (pin "2") (pinfunction "2_2") (pintype "passive"))
      (node (ref "X6") (pin "7") (pinfunction "7_7") (pintype "passive"))
      (node (ref "X6") (pin "8") (pinfunction "8_8") (pintype "passive"))
      (node (ref "X7") (pin "5") (pinfunction "5_5") (pintype "passive"))
      (node (ref "X7") (pin "6") (pinfunction "6_6") (pintype "passive"))
      (node (ref "X7") (pin "7") (pinfunction "7_7") (pintype "passive"))
      (node (ref "X7") (pin "8") (pinfunction "8_8") (pintype "passive"))
      (node (ref "X8") (pin "1") (pinfunction "1_1") (pintype "passive"))
      (node (ref "X8") (pin "2") (pinfunction "2_2") (pintype "passive"))
      (node (ref "X8") (pin "7") (pinfunction "7_7") (pintype "passive"))
      (node (ref "X8") (pin "8") (pinfunction "8_8") (pintype "passive"))
    )
    (net (code "15") (name "unconnected-(DD1-EN-Pad3)") (class "Default")
      (node (ref "DD1") (pin "3") (pinfunction "EN_3") (pintype "passive+no_connect"))
    )
    (net (code "16") (name "unconnected-(DD2-NC-Pad5)") (class "Default")
      (node (ref "DD2") (pin "5") (pinfunction "NC_5") (pintype "passive+no_connect"))
    )
  )
)
